# Analog.net
KiCad netlist of a schematic drawn in Altium Designer
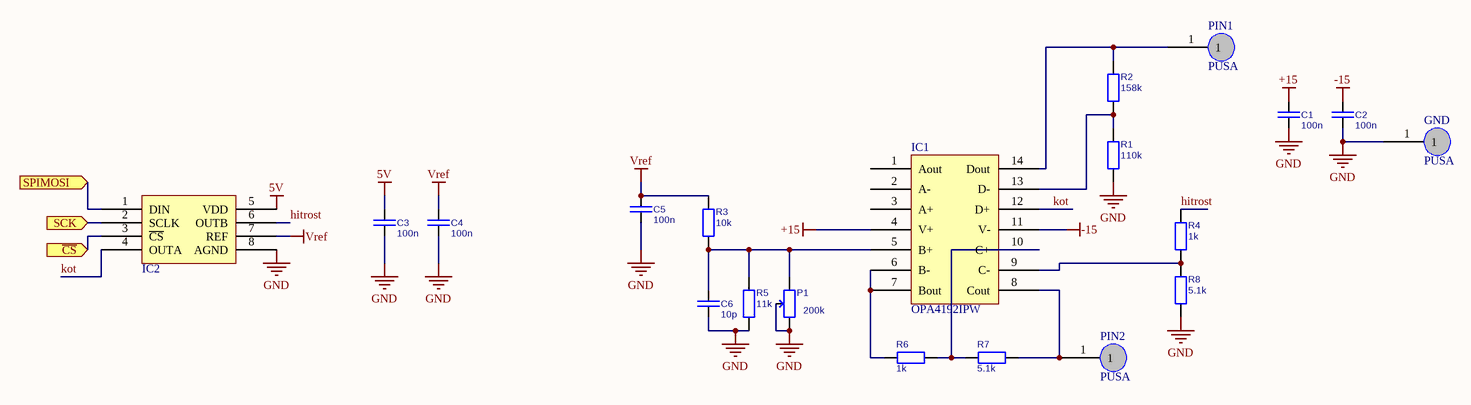
[diagram p0: Analog.SchDoc]

(export (version "E")
  (design (tool "Eeschema 10.0.6"))
  (components
    (comp (ref "C1")
      (value "100n")
      (footprint "C0603")
      (description "Capacitor")
      (libsource (lib "General") (part "C"))
    )
    (comp (ref "C2")
      (value "100n")
      (footprint "C0603")
      (description "Capacitor")
      (libsource (lib "General") (part "C"))
    )
    (comp (ref "C3")
      (value "100n")
      (footprint "C0603")
      (description "Capacitor")
      (libsource (lib "General") (part "C"))
    )
    (comp (ref "C4")
      (value "100n")
      (footprint "C0603")
      (description "Capacitor")
      (libsource (lib "General") (part "C"))
    )
    (comp (ref "C5")
      (value "100n")
      (footprint "C0603")
      (description "Capacitor")
      (libsource (lib "General") (part "C"))
    )
    (comp (ref "C6")
      (value "10p")
      (footprint "C0603")
      (description "Capacitor")
      (libsource (lib "General") (part "C"))
    )
    (comp (ref "GND") (value "PUSA") (footprint "PUSA") (libsource (lib "2016-11-04_16-51-30") (part "PUSA")))
    (comp (ref "IC1")
      (value "OPA4192IPW")
      (footprint "OPA4192")
      (libsource (lib "2016-11-04_16-51-30") (part "OPA4192IPW onepack"))
    )
    (comp (ref "IC2")
      (value "TLV5618ACD")
      (footprint "TLV5618ACD")
      (libsource (lib "2016-11-04_16-51-30") (part "TLV5618ACD"))
    )
    (comp (ref "P1")
      (value "200k")
      (footprint "Bourns_3266W")
      (description "POTENTIOMETER")
      (libsource (lib "General") (part "POT"))
    )
    (comp (ref "PIN1")
      (value "PUSA")
      (footprint "PUSA")
      (libsource (lib "2016-11-04_16-51-30") (part "PUSA"))
    )
    (comp (ref "PIN2")
      (value "PUSA")
      (footprint "PUSA")
      (libsource (lib "2016-11-04_16-51-30") (part "PUSA"))
    )
    (comp (ref "R1")
      (value "110k")
      (footprint "R0603")
      (description "R")
      (libsource (lib "General") (part "R"))
    )
    (comp (ref "R2")
      (value "158k")
      (footprint "R0603")
      (description "R")
      (libsource (lib "General") (part "R"))
    )
    (comp (ref "R3")
      (value "10k")
      (footprint "R0603")
      (description "R")
      (libsource (lib "General") (part "R"))
    )
    (comp (ref "R4")
      (value "1k")
      (footprint "R0603")
      (description "R")
      (libsource (lib "General") (part "R"))
    )
    (comp (ref "R5")
      (value "11k")
      (footprint "R0603")
      (description "R")
      (libsource (lib "General") (part "R"))
    )
    (comp (ref "R6")
      (value "1k")
      (footprint "R0603")
      (description "R")
      (libsource (lib "General") (part "R"))
    )
    (comp (ref "R7")
      (value "5.1k")
      (footprint "R0603")
      (description "R")
      (libsource (lib "General") (part "R"))
    )
    (comp (ref "R8")
      (value "5.1k")
      (footprint "R0603")
      (description "R")
      (libsource (lib "General") (part "R"))
    )
  )
  (nets
    (net (code "1") (name "+15") (class "Default")
      (node (ref "C1") (pin "1") (pinfunction "1_1") (pintype "passive"))
      (node (ref "IC1") (pin "4") (pinfunction "V+_4") (pintype "passive"))
    )
    (net (code "2") (name "-15") (class "Default")
      (node (ref "C2") (pin "1") (pinfunction "1_1") (pintype "passive"))
      (node (ref "IC1") (pin "11") (pinfunction "V-_11") (pintype "passive"))
    )
    (net (code "3") (name "/SCK") (class "Default")
      (node (ref "IC2") (pin "2") (pinfunction "SCLK_2") (pintype "passive"))
    )
    (net (code "4") (name "/SPIMOSI") (class "Default")
      (node (ref "IC2") (pin "1") (pinfunction "DIN_1") (pintype "passive"))
    )
    (net (code "5") (name "/hitrost") (class "Default")
      (node (ref "IC2") (pin "6") (pinfunction "OUTB_6") (pintype "passive"))
      (node (ref "R4") (pin "2") (pintype "passive"))
    )
    (net (code "6") (name "/kot") (class "Default")
      (node (ref "IC1") (pin "12") (pinfunction "D+_12") (pintype "passive"))
      (node (ref "IC2") (pin "4") (pinfunction "OUTA_4") (pintype "passive"))
    )
    (net (code "7") (name "/~{CS}") (class "Default")
      (node (ref "IC2") (pin "3") (pinfunction "~{CS}_3") (pintype "passive"))
    )
    (net (code "8") (name "5V") (class "Default")
      (node (ref "C3") (pin "1") (pinfunction "1_1") (pintype "passive"))
      (node (ref "IC2") (pin "5") (pinfunction "VDD_5") (pintype "passive"))
    )
    (net (code "9") (name "GND") (class "Default")
      (node (ref "C1") (pin "2") (pinfunction "2_2") (pintype "passive"))
      (node (ref "C2") (pin "2") (pinfunction "2_2") (pintype "passive"))
      (node (ref "C3") (pin "2") (pinfunction "2_2") (pintype "passive"))
      (node (ref "C4") (pin "2") (pinfunction "2_2") (pintype "passive"))
      (node (ref "C5") (pin "2") (pinfunction "2_2") (pintype "passive"))
      (node (ref "C6") (pin "2") (pinfunction "2_2") (pintype "passive"))
      (node (ref "GND") (pin "1") (pinfunction "1_1") (pintype "passive"))
      (node (ref "IC2") (pin "8") (pinfunction "AGND_8") (pintype "passive"))
      (node (ref "P1") (pin "2") (pinfunction "2_2") (pintype "passive"))
      (node (ref "P1") (pin "3") (pinfunction "3_3") (pintype "passive"))
      (node (ref "R1") (pin "2") (pintype "passive"))
      (node (ref "R5") (pin "2") (pintype "passive"))
      (node (ref "R8") (pin "2") (pintype "passive"))
    )
    (net (code "10") (name "Net-(IC1-B+)") (class "Default")
      (node (ref "C6") (pin "1") (pinfunction "1_1") (pintype "passive"))
      (node (ref "IC1") (pin "5") (pinfunction "B+_5") (pintype "passive"))
      (node (ref "P1") (pin "1") (pinfunction "1_1") (pintype "passive"))
      (node (ref "R3") (pin "2") (pintype "passive"))
      (node (ref "R5") (pin "1") (pintype "passive"))
    )
    (net (code "11") (name "Net-(IC1-B-)") (class "Default")
      (node (ref "IC1") (pin "6") (pinfunction "B-_6") (pintype "passive"))
      (node (ref "IC1") (pin "7") (pinfunction "Bout_7") (pintype "passive"))
      (node (ref "R6") (pin "2") (pintype "passive"))
    )
    (net (code "12") (name "Net-(IC1-C+)") (class "Default")
      (node (ref "IC1") (pin "10") (pinfunction "C+_10") (pintype "passive"))
      (node (ref "R6") (pin "1") (pintype "passive"))
      (node (ref "R7") (pin "2") (pintype "passive"))
    )
    (net (code "13") (name "Net-(IC1-C-)") (class "Default")
      (node (ref "IC1") (pin "9") (pinfunction "C-_9") (pintype "passive"))
      (node (ref "R4") (pin "1") (pintype "passive"))
      (node (ref "R8") (pin "1") (pintype "passive"))
    )
    (net (code "14") (name "Net-(IC1-Cout)") (class "Default")
      (node (ref "IC1") (pin "8") (pinfunction "Cout_8") (pintype "passive"))
      (node (ref "PIN2") (pin "1") (pinfunction "1_1") (pintype "passive"))
      (node (ref "R7") (pin "1") (pintype "passive"))
    )
    (net (code "15") (name "Net-(IC1-D-)") (class "Default")
      (node (ref "IC1") (pin "13") (pinfunction "D-_13") (pintype "passive"))
      (node (ref "R1") (pin "1") (pintype "passive"))
      (node (ref "R2") (pin "2") (pintype "passive"))
    )
    (net (code "16") (name "Net-(IC1-Dout)") (class "Default")
      (node (ref "IC1") (pin "14") (pinfunction "Dout_14") (pintype "passive"))
      (node (ref "PIN1") (pin "1") (pinfunction "1_1") (pintype "passive"))
      (node (ref "R2") (pin "1") (pintype "passive"))
    )
    (net (code "17") (name "Vref") (class "Default")
      (node (ref "C4") (pin "1") (pinfunction "1_1") (pintype "passive"))
      (node (ref "C5") (pin "1") (pinfunction "1_1") (pintype "passive"))
      (node (ref "IC2") (pin "7") (pinfunction "REF_7") (pintype "passive"))
      (node (ref "R3") (pin "1") (pintype "passive"))
    )
    (net (code "18") (name "unconnected-(IC1-A+-Pad3)") (class "Default")
      (node (ref "IC1") (pin "3") (pinfunction "A+_3") (pintype "passive"))
    )
    (net (code "19") (name "unconnected-(IC1-A--Pad2)") (class "Default")
      (node (ref "IC1") (pin "2") (pinfunction "A-_2") (pintype "passive"))
    )
    (net (code "20") (name "unconnected-(IC1-Aout-Pad1)") (class "Default")
      (node (ref "IC1") (pin "1") (pinfunction "Aout_1") (pintype "passive"))
    )
  )
)
